# Proto_FeatherWing.net
KiCad netlist of a schematic drawn in EAGLE
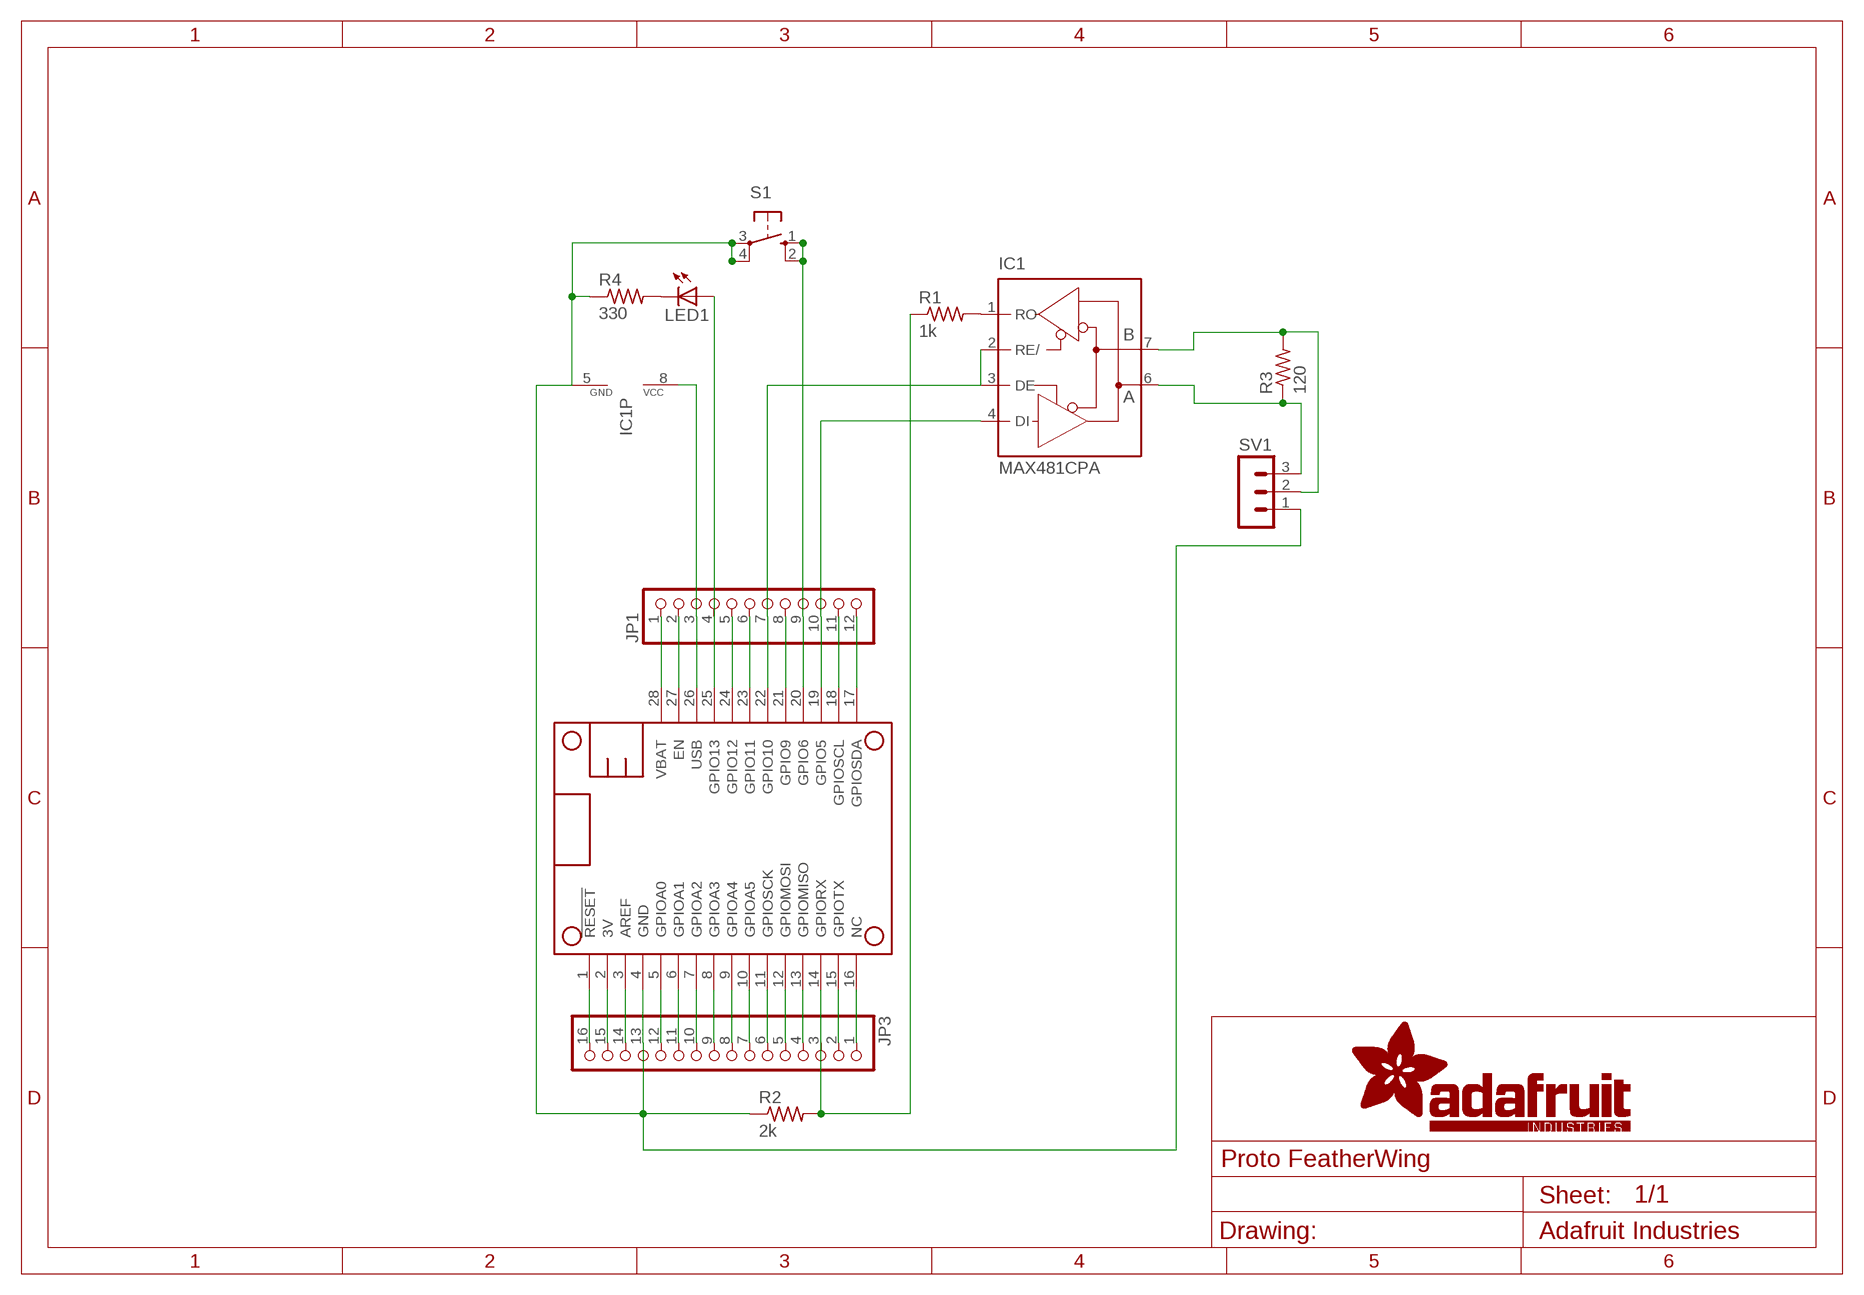
[diagram p0: schematic, sheet 1]

(export (version "E")
  (design (tool "Eeschema 10.0.6"))
  (components
    (comp (ref "IC1")
      (value "MAX481CPA")
      (footprint "eagle-import:DIL08")
      (fields (field (name "MPN") "MAX481CPA+"))
      (libsource (lib "eagle-import") (part "MAX481CPA"))
    )
    (comp (ref "JP1")
      (value "HEADER-1X1276MIL")
      (footprint "eagle-import:1X12_ROUND_76MIL")
      (libsource (lib "eagle-import") (part "HEADER-1X1276MIL"))
    )
    (comp (ref "JP3")
      (value "HEADER-1X16_76MIL")
      (footprint "eagle-import:1X16_ROUND_76MIL")
      (libsource (lib "eagle-import") (part "HEADER-1X16_76MIL"))
    )
    (comp (ref "LED1")
      (value "LED5MM")
      (footprint "eagle-import:LED5MM")
      (libsource (lib "eagle-import") (part "LED5MM"))
    )
    (comp (ref "MS1")
      (value "FEATHERWING")
      (footprint "eagle-import:FEATHERWING")
      (libsource (lib "eagle-import") (part "FEATHERWING"))
    )
    (comp (ref "R1")
      (value "1k")
      (footprint "eagle-import:0204_5")
      (libsource (lib "eagle-import") (part "R-US_0204/5"))
    )
    (comp (ref "R2")
      (value "2k")
      (footprint "eagle-import:0204_5")
      (libsource (lib "eagle-import") (part "R-US_0204/5"))
    )
    (comp (ref "R3")
      (value "120")
      (footprint "eagle-import:0204_5")
      (libsource (lib "eagle-import") (part "R-US_0204/5"))
    )
    (comp (ref "R4")
      (value "330")
      (footprint "eagle-import:0204_5")
      (libsource (lib "eagle-import") (part "R-US_0204/5"))
    )
    (comp (ref "S1")
      (value "10-XX")
      (footprint "eagle-import:B3F-10XX")
      (fields (field (name "MPN") "B3F-1000"))
      (libsource (lib "eagle-import") (part "10-XX"))
    )
    (comp (ref "SV1")
      (value "MA03-1")
      (footprint "eagle-import:MA03-1")
      (libsource (lib "eagle-import") (part "MA03-1"))
    )
  )
  (nets
    (net (code "1") (name "Net-(IC1A-A)") (class "Default")
      (node (ref "IC1") (pin "6") (pinfunction "A_6") (pintype "passive"))
      (node (ref "R3") (pin "1") (pinfunction "1_1") (pintype "passive"))
      (node (ref "SV1") (pin "3") (pinfunction "3_3") (pintype "passive"))
    )
    (net (code "2") (name "Net-(IC1A-B)") (class "Default")
      (node (ref "IC1") (pin "7") (pinfunction "B_7") (pintype "passive"))
      (node (ref "R3") (pin "2") (pinfunction "2_2") (pintype "passive"))
      (node (ref "SV1") (pin "2") (pinfunction "2_2") (pintype "passive"))
    )
    (net (code "3") (name "Net-(IC1A-DE)") (class "Default")
      (node (ref "IC1") (pin "2") (pinfunction "RE/_2") (pintype "input"))
      (node (ref "IC1") (pin "3") (pinfunction "DE_3") (pintype "input"))
      (node (ref "JP1") (pin "7") (pinfunction "7_7") (pintype "passive"))
      (node (ref "MS1") (pin "22") (pinfunction "GPIO10_22") (pintype "bidirectional"))
    )
    (net (code "4") (name "Net-(IC1A-DI)") (class "Default")
      (node (ref "IC1") (pin "4") (pinfunction "DI_4") (pintype "input"))
      (node (ref "JP1") (pin "10") (pinfunction "10_10") (pintype "passive"))
      (node (ref "MS1") (pin "19") (pinfunction "GPIO5_19") (pintype "bidirectional"))
    )
    (net (code "5") (name "Net-(IC1A-RO)") (class "Default")
      (node (ref "IC1") (pin "1") (pinfunction "RO_1") (pintype "output"))
      (node (ref "R1") (pin "2") (pinfunction "2_2") (pintype "passive"))
    )
    (net (code "6") (name "Net-(IC1B-GND)") (class "Default")
      (node (ref "IC1") (pin "5") (pinfunction "GND_5") (pintype "power_in"))
      (node (ref "JP3") (pin "13") (pinfunction "13_13") (pintype "passive"))
      (node (ref "MS1") (pin "4") (pinfunction "GND_4") (pintype "power_in"))
      (node (ref "R2") (pin "1") (pinfunction "1_1") (pintype "passive"))
      (node (ref "R4") (pin "1") (pinfunction "1_1") (pintype "passive"))
      (node (ref "S1") (pin "3") (pinfunction "P_3") (pintype "passive"))
      (node (ref "S1") (pin "4") (pinfunction "P1_4") (pintype "passive"))
      (node (ref "SV1") (pin "1") (pinfunction "1_1") (pintype "passive"))
    )
    (net (code "7") (name "Net-(IC1B-VCC)") (class "Default")
      (node (ref "IC1") (pin "8") (pinfunction "VCC_8") (pintype "power_in"))
      (node (ref "JP1") (pin "3") (pinfunction "3_3") (pintype "passive"))
      (node (ref "MS1") (pin "26") (pinfunction "USB_26") (pintype "power_in"))
    )
    (net (code "8") (name "Net-(LED1-C)") (class "Default")
      (node (ref "LED1") (pin "K") (pinfunction "C_K") (pintype "passive"))
      (node (ref "R4") (pin "2") (pinfunction "2_2") (pintype "passive"))
    )
    (net (code "9") (name "Net-(MS1-3V)") (class "Default")
      (node (ref "JP3") (pin "15") (pinfunction "15_15") (pintype "passive"))
      (node (ref "MS1") (pin "2") (pinfunction "3V_2") (pintype "power_in"))
    )
    (net (code "10") (name "Net-(MS1-AREF)") (class "Default")
      (node (ref "JP3") (pin "14") (pinfunction "14_14") (pintype "passive"))
      (node (ref "MS1") (pin "3") (pinfunction "AREF_3") (pintype "passive"))
    )
    (net (code "11") (name "Net-(MS1-EN)") (class "Default")
      (node (ref "JP1") (pin "2") (pinfunction "2_2") (pintype "passive"))
      (node (ref "MS1") (pin "27") (pinfunction "EN_27") (pintype "passive"))
    )
    (net (code "12") (name "Net-(MS1-GPIO6)") (class "Default")
      (node (ref "JP1") (pin "9") (pinfunction "9_9") (pintype "passive"))
      (node (ref "MS1") (pin "20") (pinfunction "GPIO6_20") (pintype "bidirectional"))
      (node (ref "S1") (pin "1") (pinfunction "S_1") (pintype "passive"))
      (node (ref "S1") (pin "2") (pinfunction "S1_2") (pintype "passive"))
    )
    (net (code "13") (name "Net-(MS1-GPIO9)") (class "Default")
      (node (ref "JP1") (pin "8") (pinfunction "8_8") (pintype "passive"))
      (node (ref "MS1") (pin "21") (pinfunction "GPIO9_21") (pintype "bidirectional"))
    )
    (net (code "14") (name "Net-(MS1-GPIO11)") (class "Default")
      (node (ref "JP1") (pin "6") (pinfunction "6_6") (pintype "passive"))
      (node (ref "MS1") (pin "23") (pinfunction "GPIO11_23") (pintype "bidirectional"))
    )
    (net (code "15") (name "Net-(MS1-GPIO12)") (class "Default")
      (node (ref "JP1") (pin "5") (pinfunction "5_5") (pintype "passive"))
      (node (ref "MS1") (pin "24") (pinfunction "GPIO12_24") (pintype "bidirectional"))
    )
    (net (code "16") (name "Net-(MS1-GPIO13)") (class "Default")
      (node (ref "JP1") (pin "4") (pinfunction "4_4") (pintype "passive"))
      (node (ref "LED1") (pin "A") (pinfunction "A_A") (pintype "passive"))
      (node (ref "MS1") (pin "25") (pinfunction "GPIO13_25") (pintype "bidirectional"))
    )
    (net (code "17") (name "Net-(MS1-GPIOA0)") (class "Default")
      (node (ref "JP3") (pin "12") (pinfunction "12_12") (pintype "passive"))
      (node (ref "MS1") (pin "5") (pinfunction "GPIOA0_5") (pintype "bidirectional"))
    )
    (net (code "18") (name "Net-(MS1-GPIOA1)") (class "Default")
      (node (ref "JP3") (pin "11") (pinfunction "11_11") (pintype "passive"))
      (node (ref "MS1") (pin "6") (pinfunction "GPIOA1_6") (pintype "bidirectional"))
    )
    (net (code "19") (name "Net-(MS1-GPIOA2)") (class "Default")
      (node (ref "JP3") (pin "10") (pinfunction "10_10") (pintype "passive"))
      (node (ref "MS1") (pin "7") (pinfunction "GPIOA2_7") (pintype "bidirectional"))
    )
    (net (code "20") (name "Net-(MS1-GPIOA3)") (class "Default")
      (node (ref "JP3") (pin "9") (pinfunction "9_9") (pintype "passive"))
      (node (ref "MS1") (pin "8") (pinfunction "GPIOA3_8") (pintype "bidirectional"))
    )
    (net (code "21") (name "Net-(MS1-GPIOA4)") (class "Default")
      (node (ref "JP3") (pin "8") (pinfunction "8_8") (pintype "passive"))
      (node (ref "MS1") (pin "9") (pinfunction "GPIOA4_9") (pintype "bidirectional"))
    )
    (net (code "22") (name "Net-(MS1-GPIOA5)") (class "Default")
      (node (ref "JP3") (pin "7") (pinfunction "7_7") (pintype "passive"))
      (node (ref "MS1") (pin "10") (pinfunction "GPIOA5_10") (pintype "bidirectional"))
    )
    (net (code "23") (name "Net-(MS1-GPIOMISO)") (class "Default")
      (node (ref "JP3") (pin "4") (pinfunction "4_4") (pintype "passive"))
      (node (ref "MS1") (pin "13") (pinfunction "GPIOMISO_13") (pintype "bidirectional"))
    )
    (net (code "24") (name "Net-(MS1-GPIOMOSI)") (class "Default")
      (node (ref "JP3") (pin "5") (pinfunction "5_5") (pintype "passive"))
      (node (ref "MS1") (pin "12") (pinfunction "GPIOMOSI_12") (pintype "bidirectional"))
    )
    (net (code "25") (name "Net-(MS1-GPIORX)") (class "Default")
      (node (ref "JP3") (pin "3") (pinfunction "3_3") (pintype "passive"))
      (node (ref "MS1") (pin "14") (pinfunction "GPIORX_14") (pintype "bidirectional"))
      (node (ref "R1") (pin "1") (pinfunction "1_1") (pintype "passive"))
      (node (ref "R2") (pin "2") (pinfunction "2_2") (pintype "passive"))
    )
    (net (code "26") (name "Net-(MS1-GPIOSCK)") (class "Default")
      (node (ref "JP3") (pin "6") (pinfunction "6_6") (pintype "passive"))
      (node (ref "MS1") (pin "11") (pinfunction "GPIOSCK_11") (pintype "bidirectional"))
    )
    (net (code "27") (name "Net-(MS1-GPIOSCL)") (class "Default")
      (node (ref "JP1") (pin "11") (pinfunction "11_11") (pintype "passive"))
      (node (ref "MS1") (pin "18") (pinfunction "GPIOSCL_18") (pintype "bidirectional"))
    )
    (net (code "28") (name "Net-(MS1-GPIOSDA)") (class "Default")
      (node (ref "JP1") (pin "12") (pinfunction "12_12") (pintype "passive"))
      (node (ref "MS1") (pin "17") (pinfunction "GPIOSDA_17") (pintype "bidirectional"))
    )
    (net (code "29") (name "Net-(MS1-GPIOTX)") (class "Default")
      (node (ref "JP3") (pin "2") (pinfunction "2_2") (pintype "passive"))
      (node (ref "MS1") (pin "15") (pinfunction "GPIOTX_15") (pintype "bidirectional"))
    )
    (net (code "30") (name "Net-(MS1-NC)") (class "Default")
      (node (ref "JP3") (pin "1") (pinfunction "1_1") (pintype "passive"))
      (node (ref "MS1") (pin "16") (pinfunction "NC_16") (pintype "passive"))
    )
    (net (code "31") (name "Net-(MS1-VBAT)") (class "Default")
      (node (ref "JP1") (pin "1") (pinfunction "1_1") (pintype "passive"))
      (node (ref "MS1") (pin "28") (pinfunction "VBAT_28") (pintype "power_in"))
    )
    (net (code "32") (name "Net-(MS1-~{RESET})") (class "Default")
      (node (ref "JP3") (pin "16") (pinfunction "16_16") (pintype "passive"))
      (node (ref "MS1") (pin "1") (pinfunction "~{RESET}_1") (pintype "input"))
    )
  )
)
